# ETH.net
KiCad netlist of a schematic drawn in Altium Designer
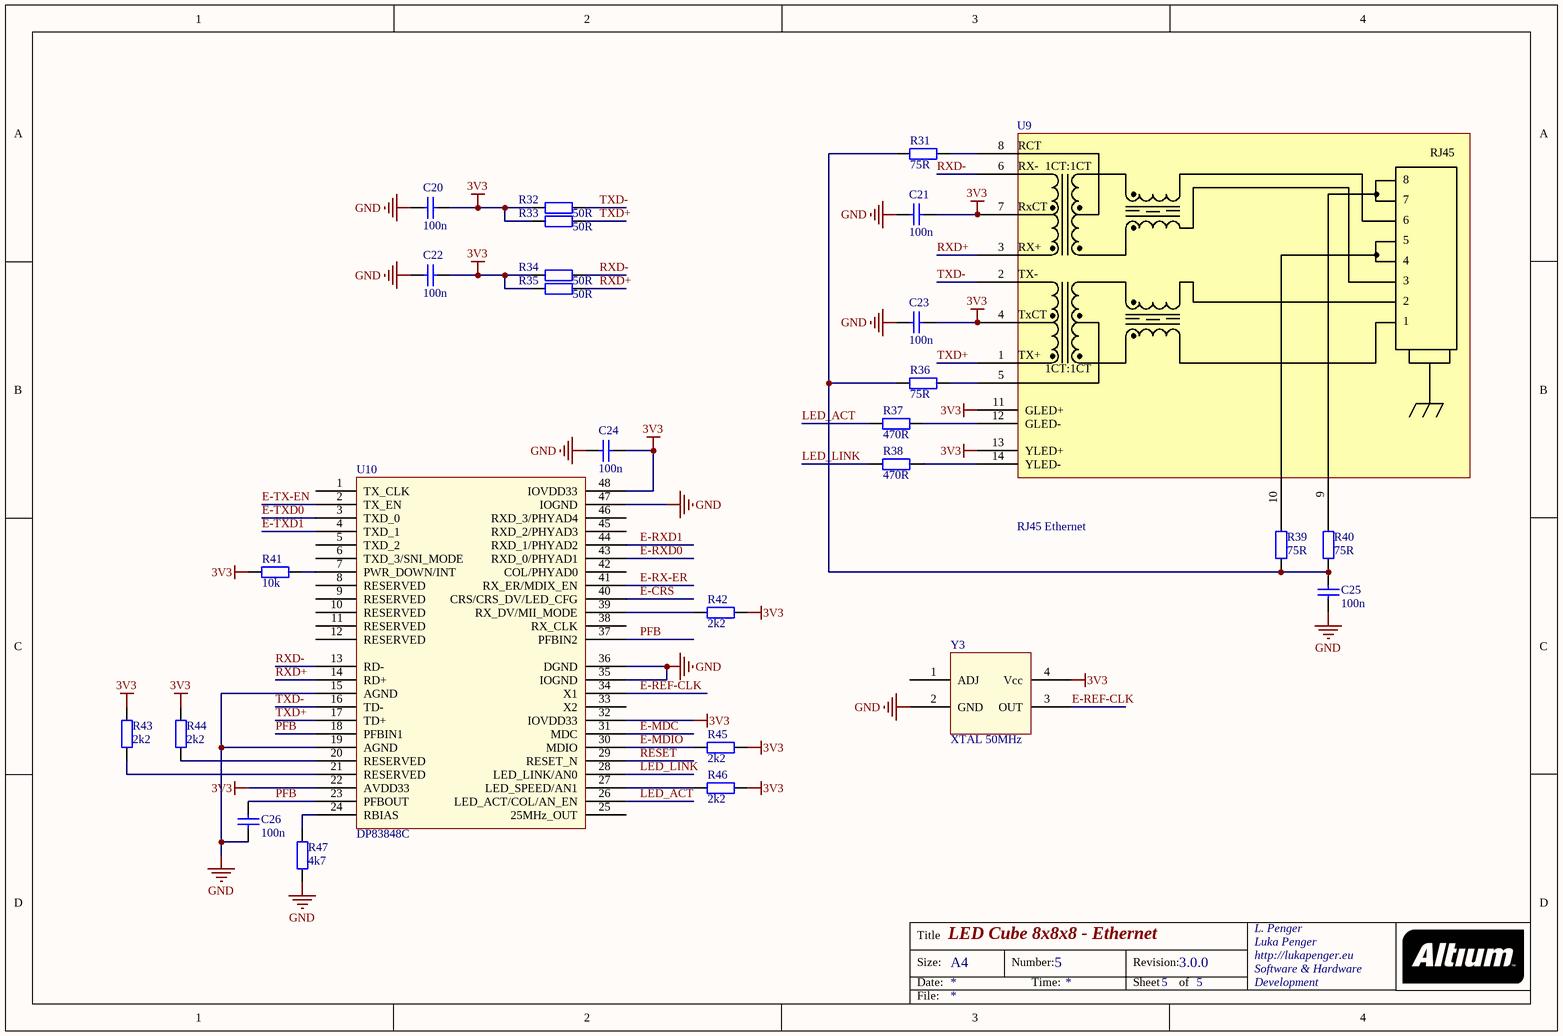
[diagram p0: ETH.SchDoc]

(export (version "E")
  (design (tool "Eeschema 10.0.6"))
  (components
    (comp (ref "C20")
      (value "100n")
      (footprint "1608[0603]")
      (description "Capacitor")
      (fields (field (name "PUBLISHER") "Altium Limited"))
      (libsource (lib "Miscellaneous Devices") (part "Cap"))
    )
    (comp (ref "C21")
      (value "100n")
      (footprint "1608[0603]")
      (description "Capacitor")
      (fields (field (name "PUBLISHER") "Altium Limited"))
      (libsource (lib "Miscellaneous Devices") (part "Cap"))
    )
    (comp (ref "C22")
      (value "100n")
      (footprint "1608[0603]")
      (description "Capacitor")
      (fields (field (name "PUBLISHER") "Altium Limited"))
      (libsource (lib "Miscellaneous Devices") (part "Cap"))
    )
    (comp (ref "C23")
      (value "100n")
      (footprint "1608[0603]")
      (description "Capacitor")
      (fields (field (name "PUBLISHER") "Altium Limited"))
      (libsource (lib "Miscellaneous Devices") (part "Cap"))
    )
    (comp (ref "C24")
      (value "100n")
      (footprint "1608[0603]")
      (description "Capacitor")
      (fields (field (name "PUBLISHER") "Altium Limited"))
      (libsource (lib "Miscellaneous Devices") (part "Cap"))
    )
    (comp (ref "C25")
      (value "100n")
      (footprint "1608[0603]")
      (description "Capacitor")
      (fields (field (name "PUBLISHER") "Altium Limited"))
      (libsource (lib "Miscellaneous Devices") (part "Cap"))
    )
    (comp (ref "C26")
      (value "100n")
      (footprint "6-0805_L")
      (description "Capacitor")
      (fields (field (name "PUBLISHER") "Altium Limited"))
      (libsource (lib "Miscellaneous Devices") (part "Cap"))
    )
    (comp (ref "R31")
      (value "75R")
      (footprint "1608[0603]")
      (description "Resistor")
      (fields (field (name "PUBLISHER") "Altium Limited"))
      (libsource (lib "Miscellaneous Devices") (part "Res2"))
    )
    (comp (ref "R32")
      (value "50R")
      (footprint "1608[0603]")
      (description "Resistor")
      (fields (field (name "PUBLISHER") "Altium Limited"))
      (libsource (lib "Miscellaneous Devices") (part "Res2"))
    )
    (comp (ref "R33")
      (value "50R")
      (footprint "1608[0603]")
      (description "Resistor")
      (fields (field (name "PUBLISHER") "Altium Limited"))
      (libsource (lib "Miscellaneous Devices") (part "Res2"))
    )
    (comp (ref "R34")
      (value "50R")
      (footprint "1608[0603]")
      (description "Resistor")
      (fields (field (name "PUBLISHER") "Altium Limited"))
      (libsource (lib "Miscellaneous Devices") (part "Res2"))
    )
    (comp (ref "R35")
      (value "50R")
      (footprint "1608[0603]")
      (description "Resistor")
      (fields (field (name "PUBLISHER") "Altium Limited"))
      (libsource (lib "Miscellaneous Devices") (part "Res2"))
    )
    (comp (ref "R36")
      (value "75R")
      (footprint "1608[0603]")
      (description "Resistor")
      (fields (field (name "PUBLISHER") "Altium Limited"))
      (libsource (lib "Miscellaneous Devices") (part "Res2"))
    )
    (comp (ref "R37")
      (value "470R")
      (footprint "1608[0603]")
      (description "Resistor")
      (fields (field (name "PUBLISHER") "Altium Limited"))
      (libsource (lib "Miscellaneous Devices") (part "Res2"))
    )
    (comp (ref "R38")
      (value "470R")
      (footprint "1608[0603]")
      (description "Resistor")
      (fields (field (name "PUBLISHER") "Altium Limited"))
      (libsource (lib "Miscellaneous Devices") (part "Res2"))
    )
    (comp (ref "R39")
      (value "75R")
      (footprint "1608[0603]")
      (description "Resistor")
      (fields (field (name "PUBLISHER") "Altium Limited"))
      (libsource (lib "") (part "Res2_2"))
    )
    (comp (ref "R40")
      (value "75R")
      (footprint "1608[0603]")
      (description "Resistor")
      (fields (field (name "PUBLISHER") "Altium Limited"))
      (libsource (lib "") (part "Res2_2"))
    )
    (comp (ref "R41")
      (value "10k")
      (footprint "1608[0603]")
      (description "Resistor")
      (fields (field (name "PUBLISHER") "Altium Limited"))
      (libsource (lib "Miscellaneous Devices") (part "Res2"))
    )
    (comp (ref "R42")
      (value "2k2")
      (footprint "1608[0603]")
      (description "Resistor")
      (fields (field (name "PUBLISHER") "Altium Limited"))
      (libsource (lib "Miscellaneous Devices") (part "Res2"))
    )
    (comp (ref "R43")
      (value "2k2")
      (footprint "1608[0603]")
      (description "Resistor")
      (fields (field (name "PUBLISHER") "Altium Limited"))
      (libsource (lib "") (part "Res2_1"))
    )
    (comp (ref "R44")
      (value "2k2")
      (footprint "1608[0603]")
      (description "Resistor")
      (fields (field (name "PUBLISHER") "Altium Limited"))
      (libsource (lib "") (part "Res2_2"))
    )
    (comp (ref "R45")
      (value "2k2")
      (footprint "1608[0603]")
      (description "Resistor")
      (fields (field (name "PUBLISHER") "Altium Limited"))
      (libsource (lib "Miscellaneous Devices") (part "Res2"))
    )
    (comp (ref "R46")
      (value "2k2")
      (footprint "1608[0603]")
      (description "Resistor")
      (fields (field (name "PUBLISHER") "Altium Limited"))
      (libsource (lib "Miscellaneous Devices") (part "Res2"))
    )
    (comp (ref "R47")
      (value "4k7")
      (footprint "1608[0603]")
      (description "Resistor")
      (fields (field (name "PUBLISHER") "Altium Limited"))
      (libsource (lib "") (part "Res2_1"))
    )
    (comp (ref "U9")
      (value "RJ45 Ethernet")
      (footprint "RJ45 Ethernet connector")
      (description "Ethernet Connector")
      (libsource (lib "LP_Lib") (part "RJ45 Ethernet"))
    )
    (comp (ref "U10")
      (value "DP83848C")
      (footprint "DP83848C")
      (description "Ethernet PHY")
      (libsource (lib "LP_Lib") (part "DP83848C"))
    )
    (comp (ref "Y3")
      (value "XTAL 50MHz")
      (footprint "XTAL ACT9200")
      (libsource (lib "LP_Lib") (part "XTAL ACT9200"))
    )
  )
  (nets
    (net (code "1") (name "/E-CRS") (class "Default")
      (node (ref "U10") (pin "40") (pinfunction "CRS/CRS_DV/LED_CFG_40") (pintype "passive"))
    )
    (net (code "2") (name "/E-MDC") (class "Default")
      (node (ref "U10") (pin "31") (pinfunction "MDC_31") (pintype "passive"))
    )
    (net (code "3") (name "/E-MDIO") (class "Default")
      (node (ref "R45") (pin "2") (pinfunction "2_2") (pintype "passive"))
      (node (ref "U10") (pin "30") (pinfunction "MDIO_30") (pintype "passive"))
    )
    (net (code "4") (name "/E-REF-CLK") (class "Default")
      (node (ref "U10") (pin "34") (pinfunction "X1_34") (pintype "passive"))
      (node (ref "Y3") (pin "3") (pinfunction "OUT_3") (pintype "passive"))
    )
    (net (code "5") (name "/E-RX-ER") (class "Default")
      (node (ref "U10") (pin "41") (pinfunction "RX_ER/MDIX_EN_41") (pintype "passive"))
    )
    (net (code "6") (name "/E-RXD0") (class "Default")
      (node (ref "U10") (pin "43") (pinfunction "RXD_0/PHYAD1_43") (pintype "passive"))
    )
    (net (code "7") (name "/E-RXD1") (class "Default")
      (node (ref "U10") (pin "44") (pinfunction "RXD_1/PHYAD2_44") (pintype "passive"))
    )
    (net (code "8") (name "/E-TX-EN") (class "Default")
      (node (ref "U10") (pin "2") (pinfunction "TX_EN_2") (pintype "passive"))
    )
    (net (code "9") (name "/E-TXD0") (class "Default")
      (node (ref "U10") (pin "3") (pinfunction "TXD_0_3") (pintype "passive"))
    )
    (net (code "10") (name "/E-TXD1") (class "Default")
      (node (ref "U10") (pin "4") (pinfunction "TXD_1_4") (pintype "passive"))
    )
    (net (code "11") (name "/LED_ACT") (class "Default")
      (node (ref "R37") (pin "2") (pinfunction "2_2") (pintype "passive"))
      (node (ref "U10") (pin "26") (pinfunction "LED_ACT/COL/AN_EN_26") (pintype "passive"))
    )
    (net (code "12") (name "/LED_LINK") (class "Default")
      (node (ref "R38") (pin "2") (pinfunction "2_2") (pintype "passive"))
      (node (ref "U10") (pin "28") (pinfunction "LED_LINK/AN0_28") (pintype "passive"))
    )
    (net (code "13") (name "/PFB") (class "Default")
      (node (ref "C26") (pin "1") (pinfunction "1_1") (pintype "passive"))
      (node (ref "U10") (pin "18") (pinfunction "PFBIN1_18") (pintype "passive"))
      (node (ref "U10") (pin "23") (pinfunction "PFBOUT_23") (pintype "passive"))
      (node (ref "U10") (pin "37") (pinfunction "PFBIN2_37") (pintype "passive"))
    )
    (net (code "14") (name "/RESET") (class "Default")
      (node (ref "U10") (pin "29") (pinfunction "RESET_N_29") (pintype "passive"))
    )
    (net (code "15") (name "/RXD+") (class "Default")
      (node (ref "R35") (pin "1") (pinfunction "1_1") (pintype "passive"))
      (node (ref "U10") (pin "14") (pinfunction "RD+_14") (pintype "passive"))
      (node (ref "U9") (pin "3") (pintype "passive"))
    )
    (net (code "16") (name "/RXD-") (class "Default")
      (node (ref "R34") (pin "1") (pinfunction "1_1") (pintype "passive"))
      (node (ref "U10") (pin "13") (pinfunction "RD-_13") (pintype "passive"))
      (node (ref "U9") (pin "6") (pintype "passive"))
    )
    (net (code "17") (name "/TXD+") (class "Default")
      (node (ref "R33") (pin "1") (pinfunction "1_1") (pintype "passive"))
      (node (ref "U10") (pin "17") (pinfunction "TD+_17") (pintype "passive"))
      (node (ref "U9") (pin "1") (pintype "passive"))
    )
    (net (code "18") (name "/TXD-") (class "Default")
      (node (ref "R32") (pin "1") (pinfunction "1_1") (pintype "passive"))
      (node (ref "U10") (pin "16") (pinfunction "TD-_16") (pintype "passive"))
      (node (ref "U9") (pin "2") (pintype "passive"))
    )
    (net (code "19") (name "3V3") (class "Default")
      (node (ref "C20") (pin "2") (pinfunction "2_2") (pintype "passive"))
      (node (ref "C21") (pin "2") (pinfunction "2_2") (pintype "passive"))
      (node (ref "C22") (pin "2") (pinfunction "2_2") (pintype "passive"))
      (node (ref "C23") (pin "2") (pinfunction "2_2") (pintype "passive"))
      (node (ref "C24") (pin "2") (pinfunction "2_2") (pintype "passive"))
      (node (ref "R32") (pin "2") (pinfunction "2_2") (pintype "passive"))
      (node (ref "R33") (pin "2") (pinfunction "2_2") (pintype "passive"))
      (node (ref "R34") (pin "2") (pinfunction "2_2") (pintype "passive"))
      (node (ref "R35") (pin "2") (pinfunction "2_2") (pintype "passive"))
      (node (ref "R41") (pin "2") (pinfunction "2_2") (pintype "passive"))
      (node (ref "R42") (pin "1") (pinfunction "1_1") (pintype "passive"))
      (node (ref "R43") (pin "1") (pinfunction "1_1") (pintype "passive"))
      (node (ref "R44") (pin "2") (pinfunction "2_2") (pintype "passive"))
      (node (ref "R45") (pin "1") (pinfunction "1_1") (pintype "passive"))
      (node (ref "R46") (pin "1") (pinfunction "1_1") (pintype "passive"))
      (node (ref "U10") (pin "22") (pinfunction "AVDD33_22") (pintype "passive"))
      (node (ref "U10") (pin "32") (pinfunction "IOVDD33_32") (pintype "passive"))
      (node (ref "U10") (pin "48") (pinfunction "IOVDD33_48") (pintype "passive"))
      (node (ref "U9") (pin "11") (pinfunction "GLED+_11") (pintype "passive"))
      (node (ref "U9") (pin "13") (pinfunction "YLED+_13") (pintype "passive"))
      (node (ref "U9") (pin "4") (pintype "passive"))
      (node (ref "U9") (pin "7") (pintype "passive"))
      (node (ref "Y3") (pin "4") (pinfunction "Vcc_4") (pintype "passive"))
    )
    (net (code "20") (name "GND") (class "Default")
      (node (ref "C20") (pin "1") (pinfunction "1_1") (pintype "passive"))
      (node (ref "C21") (pin "1") (pinfunction "1_1") (pintype "passive"))
      (node (ref "C22") (pin "1") (pinfunction "1_1") (pintype "passive"))
      (node (ref "C23") (pin "1") (pinfunction "1_1") (pintype "passive"))
      (node (ref "C24") (pin "1") (pinfunction "1_1") (pintype "passive"))
      (node (ref "C25") (pin "2") (pinfunction "2_2") (pintype "passive"))
      (node (ref "C26") (pin "2") (pinfunction "2_2") (pintype "passive"))
      (node (ref "R47") (pin "2") (pinfunction "2_2") (pintype "passive"))
      (node (ref "U10") (pin "15") (pinfunction "AGND_15") (pintype "passive"))
      (node (ref "U10") (pin "19") (pinfunction "AGND_19") (pintype "passive"))
      (node (ref "U10") (pin "35") (pinfunction "IOGND_35") (pintype "passive"))
      (node (ref "U10") (pin "36") (pinfunction "DGND_36") (pintype "passive"))
      (node (ref "U10") (pin "47") (pinfunction "IOGND_47") (pintype "passive"))
      (node (ref "Y3") (pin "2") (pinfunction "GND_2") (pintype "passive"))
    )
    (net (code "21") (name "Net-(C25-Pad1)") (class "Default")
      (node (ref "C25") (pin "1") (pinfunction "1_1") (pintype "passive"))
      (node (ref "R31") (pin "2") (pinfunction "2_2") (pintype "passive"))
      (node (ref "R36") (pin "2") (pinfunction "2_2") (pintype "passive"))
      (node (ref "R39") (pin "1") (pinfunction "1_1") (pintype "passive"))
      (node (ref "R40") (pin "1") (pinfunction "1_1") (pintype "passive"))
    )
    (net (code "22") (name "Net-(R31-Pad1)") (class "Default")
      (node (ref "R31") (pin "1") (pinfunction "1_1") (pintype "passive"))
      (node (ref "U9") (pin "8") (pintype "passive"))
    )
    (net (code "23") (name "Net-(R36-Pad1)") (class "Default")
      (node (ref "R36") (pin "1") (pinfunction "1_1") (pintype "passive"))
      (node (ref "U9") (pin "5") (pintype "passive"))
    )
    (net (code "24") (name "Net-(R39-Pad2)") (class "Default")
      (node (ref "R39") (pin "2") (pinfunction "2_2") (pintype "passive"))
      (node (ref "U9") (pin "10") (pintype "passive"))
    )
    (net (code "25") (name "Net-(R40-Pad2)") (class "Default")
      (node (ref "R40") (pin "2") (pinfunction "2_2") (pintype "passive"))
      (node (ref "U9") (pin "9") (pintype "passive"))
    )
    (net (code "26") (name "Net-(R43-Pad2)") (class "Default")
      (node (ref "R43") (pin "2") (pinfunction "2_2") (pintype "passive"))
      (node (ref "U10") (pin "21") (pinfunction "RESERVED_21") (pintype "passive"))
    )
    (net (code "27") (name "Net-(R44-Pad1)") (class "Default")
      (node (ref "R44") (pin "1") (pinfunction "1_1") (pintype "passive"))
      (node (ref "U10") (pin "20") (pinfunction "RESERVED_20") (pintype "passive"))
    )
    (net (code "28") (name "Net-(U9-GLED-)") (class "Default")
      (node (ref "R37") (pin "1") (pinfunction "1_1") (pintype "passive"))
      (node (ref "U9") (pin "12") (pinfunction "GLED-_12") (pintype "passive"))
    )
    (net (code "29") (name "Net-(U9-YLED-)") (class "Default")
      (node (ref "R38") (pin "1") (pinfunction "1_1") (pintype "passive"))
      (node (ref "U9") (pin "14") (pinfunction "YLED-_14") (pintype "passive"))
    )
    (net (code "30") (name "Net-(U10-LED_SPEED{slash}AN1)") (class "Default")
      (node (ref "R46") (pin "2") (pinfunction "2_2") (pintype "passive"))
      (node (ref "U10") (pin "27") (pinfunction "LED_SPEED/AN1_27") (pintype "passive"))
    )
    (net (code "31") (name "Net-(U10-PWR_DOWN{slash}INT)") (class "Default")
      (node (ref "R41") (pin "1") (pinfunction "1_1") (pintype "passive"))
      (node (ref "U10") (pin "7") (pinfunction "PWR_DOWN/INT_7") (pintype "passive"))
    )
    (net (code "32") (name "Net-(U10-RBIAS)") (class "Default")
      (node (ref "R47") (pin "1") (pinfunction "1_1") (pintype "passive"))
      (node (ref "U10") (pin "24") (pinfunction "RBIAS_24") (pintype "passive"))
    )
    (net (code "33") (name "Net-(U10-RX_DV{slash}MII_MODE)") (class "Default")
      (node (ref "R42") (pin "2") (pinfunction "2_2") (pintype "passive"))
      (node (ref "U10") (pin "39") (pinfunction "RX_DV/MII_MODE_39") (pintype "passive"))
    )
    (net (code "34") (name "unconnected-(U10-25MHz_OUT-Pad25)") (class "Default")
      (node (ref "U10") (pin "25") (pinfunction "25MHz_OUT_25") (pintype "passive"))
    )
    (net (code "35") (name "unconnected-(U10-COL{slash}PHYAD0-Pad42)") (class "Default")
      (node (ref "U10") (pin "42") (pinfunction "COL/PHYAD0_42") (pintype "passive"))
    )
    (net (code "36") (name "unconnected-(U10-RESERVED-Pad8)") (class "Default")
      (node (ref "U10") (pin "8") (pinfunction "RESERVED_8") (pintype "passive"))
    )
    (net (code "37") (name "unconnected-(U10-RESERVED-Pad9)") (class "Default")
      (node (ref "U10") (pin "9") (pinfunction "RESERVED_9") (pintype "passive"))
    )
    (net (code "38") (name "unconnected-(U10-RESERVED-Pad10)") (class "Default")
      (node (ref "U10") (pin "10") (pinfunction "RESERVED_10") (pintype "passive"))
    )
    (net (code "39") (name "unconnected-(U10-RESERVED-Pad11)") (class "Default")
      (node (ref "U10") (pin "11") (pinfunction "RESERVED_11") (pintype "passive"))
    )
    (net (code "40") (name "unconnected-(U10-RESERVED-Pad12)") (class "Default")
      (node (ref "U10") (pin "12") (pinfunction "RESERVED_12") (pintype "passive"))
    )
    (net (code "41") (name "unconnected-(U10-RXD_2{slash}PHYAD3-Pad45)") (class "Default")
      (node (ref "U10") (pin "45") (pinfunction "RXD_2/PHYAD3_45") (pintype "passive"))
    )
    (net (code "42") (name "unconnected-(U10-RXD_3{slash}PHYAD4-Pad46)") (class "Default")
      (node (ref "U10") (pin "46") (pinfunction "RXD_3/PHYAD4_46") (pintype "passive"))
    )
    (net (code "43") (name "unconnected-(U10-RX_CLK-Pad38)") (class "Default")
      (node (ref "U10") (pin "38") (pinfunction "RX_CLK_38") (pintype "passive"))
    )
    (net (code "44") (name "unconnected-(U10-TXD_2-Pad5)") (class "Default")
      (node (ref "U10") (pin "5") (pinfunction "TXD_2_5") (pintype "passive"))
    )
    (net (code "45") (name "unconnected-(U10-TXD_3{slash}SNI_MODE-Pad6)") (class "Default")
      (node (ref "U10") (pin "6") (pinfunction "TXD_3/SNI_MODE_6") (pintype "passive"))
    )
    (net (code "46") (name "unconnected-(U10-TX_CLK-Pad1)") (class "Default")
      (node (ref "U10") (pin "1") (pinfunction "TX_CLK_1") (pintype "passive"))
    )
    (net (code "47") (name "unconnected-(U10-X2-Pad33)") (class "Default")
      (node (ref "U10") (pin "33") (pinfunction "X2_33") (pintype "passive"))
    )
    (net (code "48") (name "unconnected-(Y3-ADJ-Pad1)") (class "Default")
      (node (ref "Y3") (pin "1") (pinfunction "ADJ_1") (pintype "passive"))
    )
  )
)
